# out-gain.net
KiCad netlist of a schematic drawn in EAGLE
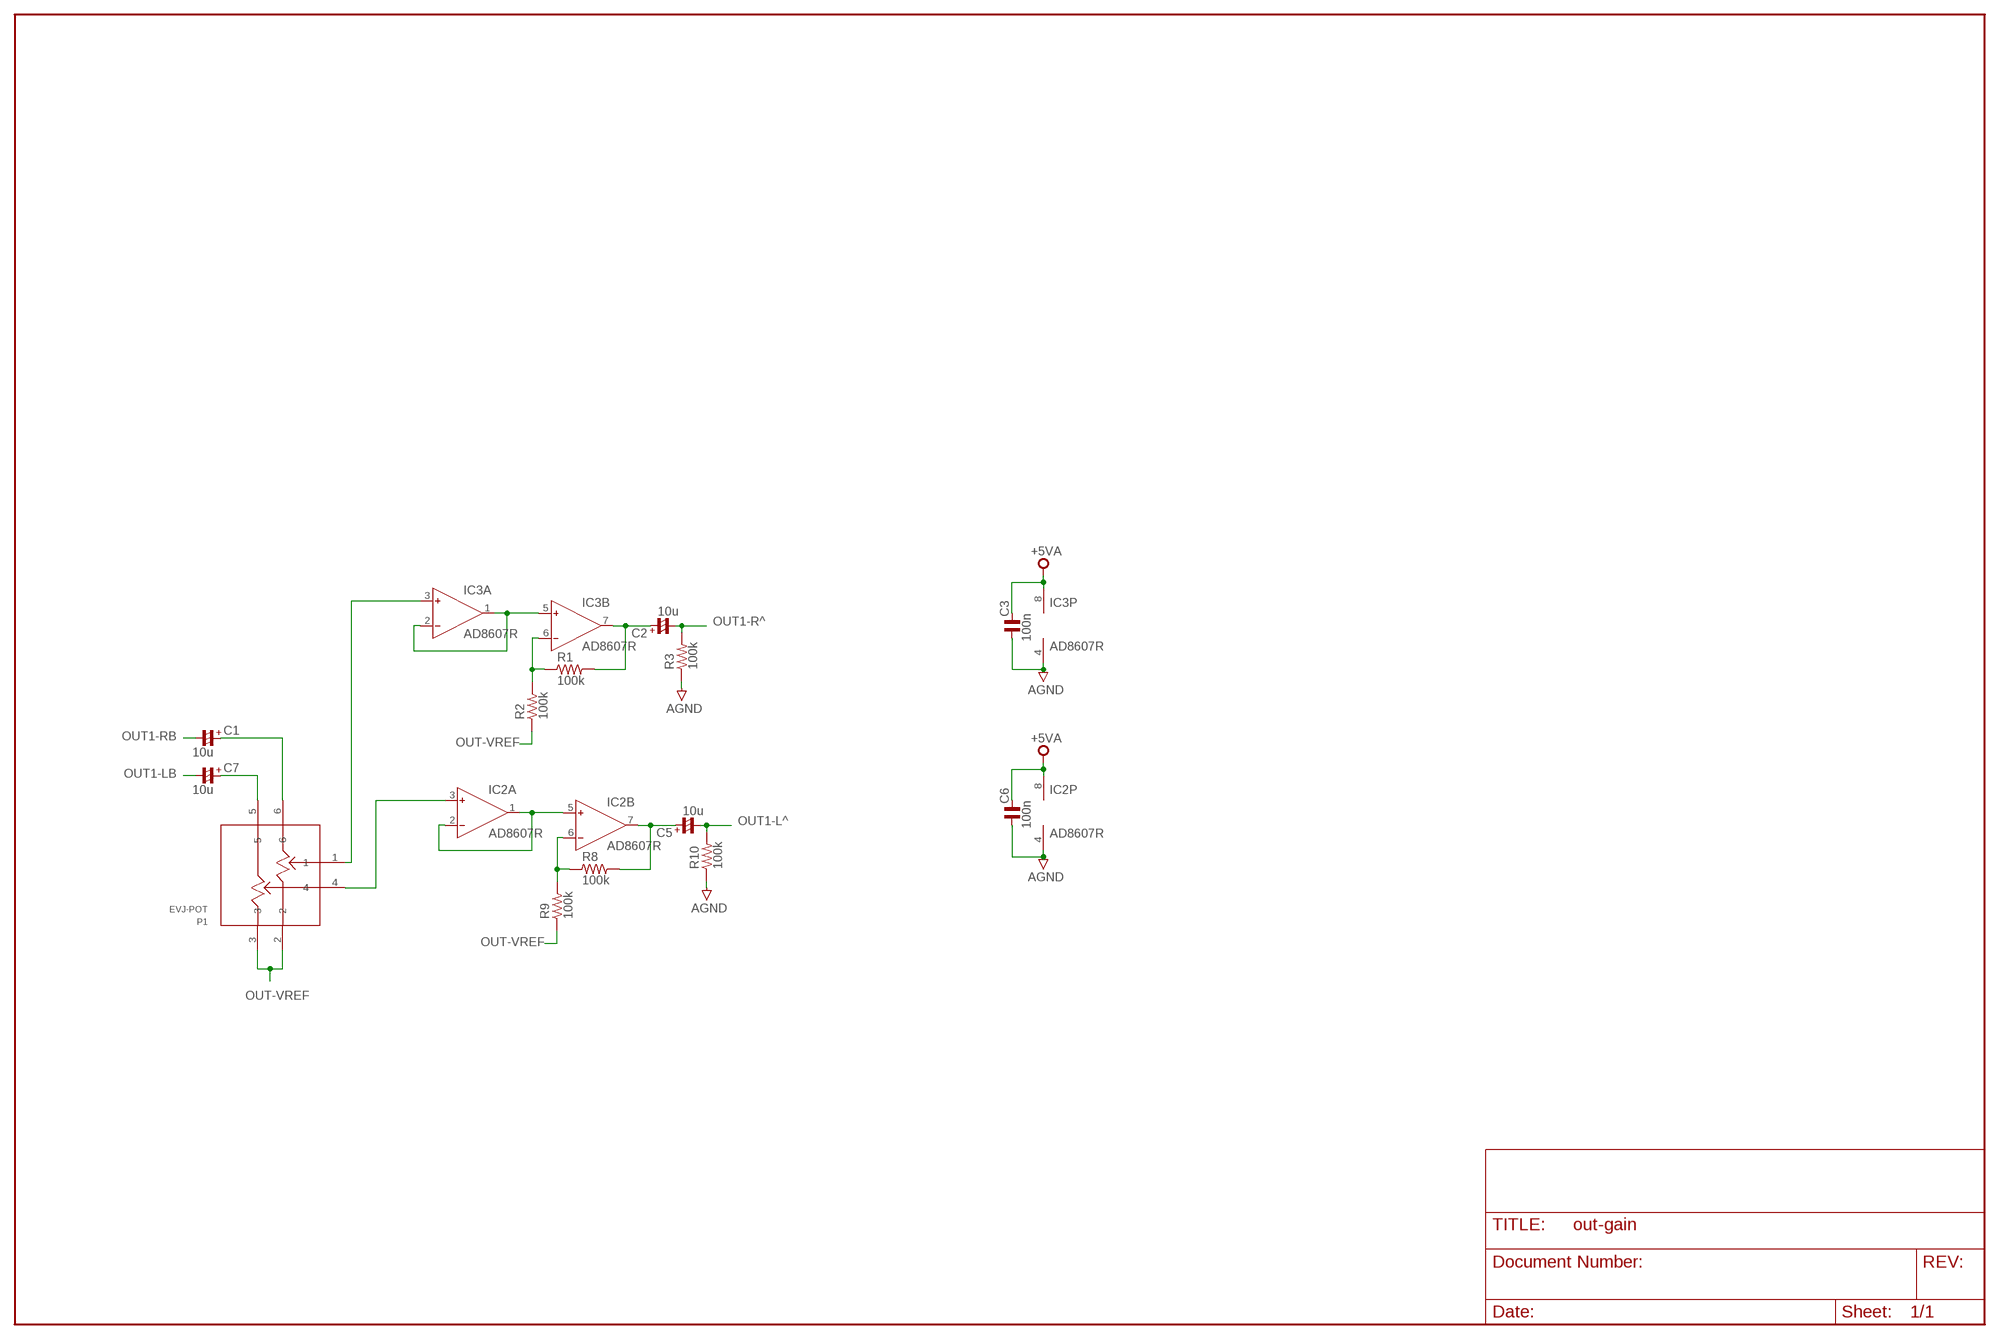
[diagram p0: schematic, sheet 1]

(export (version "E")
  (design (tool "Eeschema 10.0.6"))
  (components
    (comp (ref "C1")
      (value "10u")
      (footprint "eagle-import:C1206_T")
      (libsource (lib "eagle-import") (part "CP_1206/T"))
    )
    (comp (ref "C2")
      (value "10u")
      (footprint "eagle-import:C1206_T")
      (libsource (lib "eagle-import") (part "CP_1206/T"))
    )
    (comp (ref "C3")
      (value "100n")
      (footprint "eagle-import:C0603")
      (libsource (lib "eagle-import") (part "C_0603"))
    )
    (comp (ref "C5")
      (value "10u")
      (footprint "eagle-import:C1206_T")
      (libsource (lib "eagle-import") (part "CP_1206/T"))
    )
    (comp (ref "C6")
      (value "100n")
      (footprint "eagle-import:C0603")
      (libsource (lib "eagle-import") (part "C_0603"))
    )
    (comp (ref "C7")
      (value "10u")
      (footprint "eagle-import:C1206_T")
      (libsource (lib "eagle-import") (part "CP_1206/T"))
    )
    (comp (ref "IC2")
      (value "AD8607R")
      (footprint "eagle-import:SO8")
      (fields (field (name "MPN") "AD8607ARMZ-R2"))
      (libsource (lib "eagle-import") (part "AD8607R"))
    )
    (comp (ref "IC3")
      (value "AD8607R")
      (footprint "eagle-import:SO8")
      (fields (field (name "MPN") "AD8607ARMZ-R2"))
      (libsource (lib "eagle-import") (part "AD8607R"))
    )
    (comp (ref "P1")
      (value "EVJ-POT")
      (footprint "eagle-import:EVJ-POT")
      (libsource (lib "eagle-import") (part "EVJ-POT"))
    )
    (comp (ref "R1")
      (value "100k")
      (footprint "eagle-import:R0603")
      (libsource (lib "eagle-import") (part "R_0603"))
    )
    (comp (ref "R2")
      (value "100k")
      (footprint "eagle-import:R0603")
      (libsource (lib "eagle-import") (part "R_0603"))
    )
    (comp (ref "R3")
      (value "100k")
      (footprint "eagle-import:R0603")
      (libsource (lib "eagle-import") (part "R_0603"))
    )
    (comp (ref "R8")
      (value "100k")
      (footprint "eagle-import:R0603")
      (libsource (lib "eagle-import") (part "R_0603"))
    )
    (comp (ref "R9")
      (value "100k")
      (footprint "eagle-import:R0603")
      (libsource (lib "eagle-import") (part "R_0603"))
    )
    (comp (ref "R10")
      (value "100k")
      (footprint "eagle-import:R0603")
      (libsource (lib "eagle-import") (part "R_0603"))
    )
  )
  (nets
    (net (code "1") (name "+5VA") (class "Default")
      (node (ref "C3") (pin "2") (pinfunction "2_2") (pintype "passive"))
      (node (ref "C6") (pin "2") (pinfunction "2_2") (pintype "passive"))
      (node (ref "IC2") (pin "8") (pinfunction "V+_8") (pintype "power_in"))
      (node (ref "IC3") (pin "8") (pinfunction "V+_8") (pintype "power_in"))
    )
    (net (code "2") (name "/OUT-VREF") (class "Default")
      (node (ref "P1") (pin "2") (pinfunction "2_2") (pintype "bidirectional"))
      (node (ref "P1") (pin "3") (pinfunction "3_3") (pintype "bidirectional"))
      (node (ref "R2") (pin "1") (pinfunction "1_1") (pintype "passive"))
      (node (ref "R9") (pin "1") (pinfunction "1_1") (pintype "passive"))
    )
    (net (code "3") (name "/OUT1-LB") (class "Default")
      (node (ref "C7") (pin "-") (pinfunction "-_-") (pintype "passive"))
    )
    (net (code "4") (name "/OUT1-L^") (class "Default")
      (node (ref "C5") (pin "-") (pinfunction "-_-") (pintype "passive"))
      (node (ref "R10") (pin "2") (pinfunction "2_2") (pintype "passive"))
    )
    (net (code "5") (name "/OUT1-RB") (class "Default")
      (node (ref "C1") (pin "-") (pinfunction "-_-") (pintype "passive"))
    )
    (net (code "6") (name "/OUT1-R^") (class "Default")
      (node (ref "C2") (pin "-") (pinfunction "-_-") (pintype "passive"))
      (node (ref "R3") (pin "2") (pinfunction "2_2") (pintype "passive"))
    )
    (net (code "7") (name "AGND") (class "Default")
      (node (ref "C3") (pin "1") (pinfunction "1_1") (pintype "passive"))
      (node (ref "C6") (pin "1") (pinfunction "1_1") (pintype "passive"))
      (node (ref "IC2") (pin "4") (pinfunction "V-_4") (pintype "power_in"))
      (node (ref "IC3") (pin "4") (pinfunction "V-_4") (pintype "power_in"))
      (node (ref "R10") (pin "1") (pinfunction "1_1") (pintype "passive"))
      (node (ref "R3") (pin "1") (pinfunction "1_1") (pintype "passive"))
    )
    (net (code "8") (name "Net-(C1-Pad+)") (class "Default")
      (node (ref "C1") (pin "+") (pinfunction "+_+") (pintype "passive"))
      (node (ref "P1") (pin "6") (pinfunction "6_6") (pintype "bidirectional"))
    )
    (net (code "9") (name "Net-(C7-Pad+)") (class "Default")
      (node (ref "C7") (pin "+") (pinfunction "+_+") (pintype "passive"))
      (node (ref "P1") (pin "5") (pinfunction "5_5") (pintype "bidirectional"))
    )
    (net (code "10") (name "Net-(IC2A-IN+)") (class "Default")
      (node (ref "IC2") (pin "3") (pinfunction "IN+_3") (pintype "input"))
      (node (ref "P1") (pin "4") (pinfunction "4_4") (pintype "bidirectional"))
    )
    (net (code "11") (name "Net-(IC2A-IN-)") (class "Default")
      (node (ref "IC2") (pin "1") (pinfunction "OUT_1") (pintype "output"))
      (node (ref "IC2") (pin "2") (pinfunction "IN-_2") (pintype "input"))
      (node (ref "IC2") (pin "5") (pinfunction "IN+_5") (pintype "input"))
    )
    (net (code "12") (name "Net-(IC2B-IN-)") (class "Default")
      (node (ref "IC2") (pin "6") (pinfunction "IN-_6") (pintype "input"))
      (node (ref "R8") (pin "1") (pinfunction "1_1") (pintype "passive"))
      (node (ref "R9") (pin "2") (pinfunction "2_2") (pintype "passive"))
    )
    (net (code "13") (name "Net-(IC2B-OUT)") (class "Default")
      (node (ref "C5") (pin "+") (pinfunction "+_+") (pintype "passive"))
      (node (ref "IC2") (pin "7") (pinfunction "OUT_7") (pintype "output"))
      (node (ref "R8") (pin "2") (pinfunction "2_2") (pintype "passive"))
    )
    (net (code "14") (name "Net-(IC3A-IN+)") (class "Default")
      (node (ref "IC3") (pin "3") (pinfunction "IN+_3") (pintype "input"))
      (node (ref "P1") (pin "1") (pinfunction "1_1") (pintype "bidirectional"))
    )
    (net (code "15") (name "Net-(IC3A-IN-)") (class "Default")
      (node (ref "IC3") (pin "1") (pinfunction "OUT_1") (pintype "output"))
      (node (ref "IC3") (pin "2") (pinfunction "IN-_2") (pintype "input"))
      (node (ref "IC3") (pin "5") (pinfunction "IN+_5") (pintype "input"))
    )
    (net (code "16") (name "Net-(IC3B-IN-)") (class "Default")
      (node (ref "IC3") (pin "6") (pinfunction "IN-_6") (pintype "input"))
      (node (ref "R1") (pin "1") (pinfunction "1_1") (pintype "passive"))
      (node (ref "R2") (pin "2") (pinfunction "2_2") (pintype "passive"))
    )
    (net (code "17") (name "Net-(IC3B-OUT)") (class "Default")
      (node (ref "C2") (pin "+") (pinfunction "+_+") (pintype "passive"))
      (node (ref "IC3") (pin "7") (pinfunction "OUT_7") (pintype "output"))
      (node (ref "R1") (pin "2") (pinfunction "2_2") (pintype "passive"))
    )
  )
)
